# forkbomb19.net
KiCad netlist of a schematic drawn in EAGLE
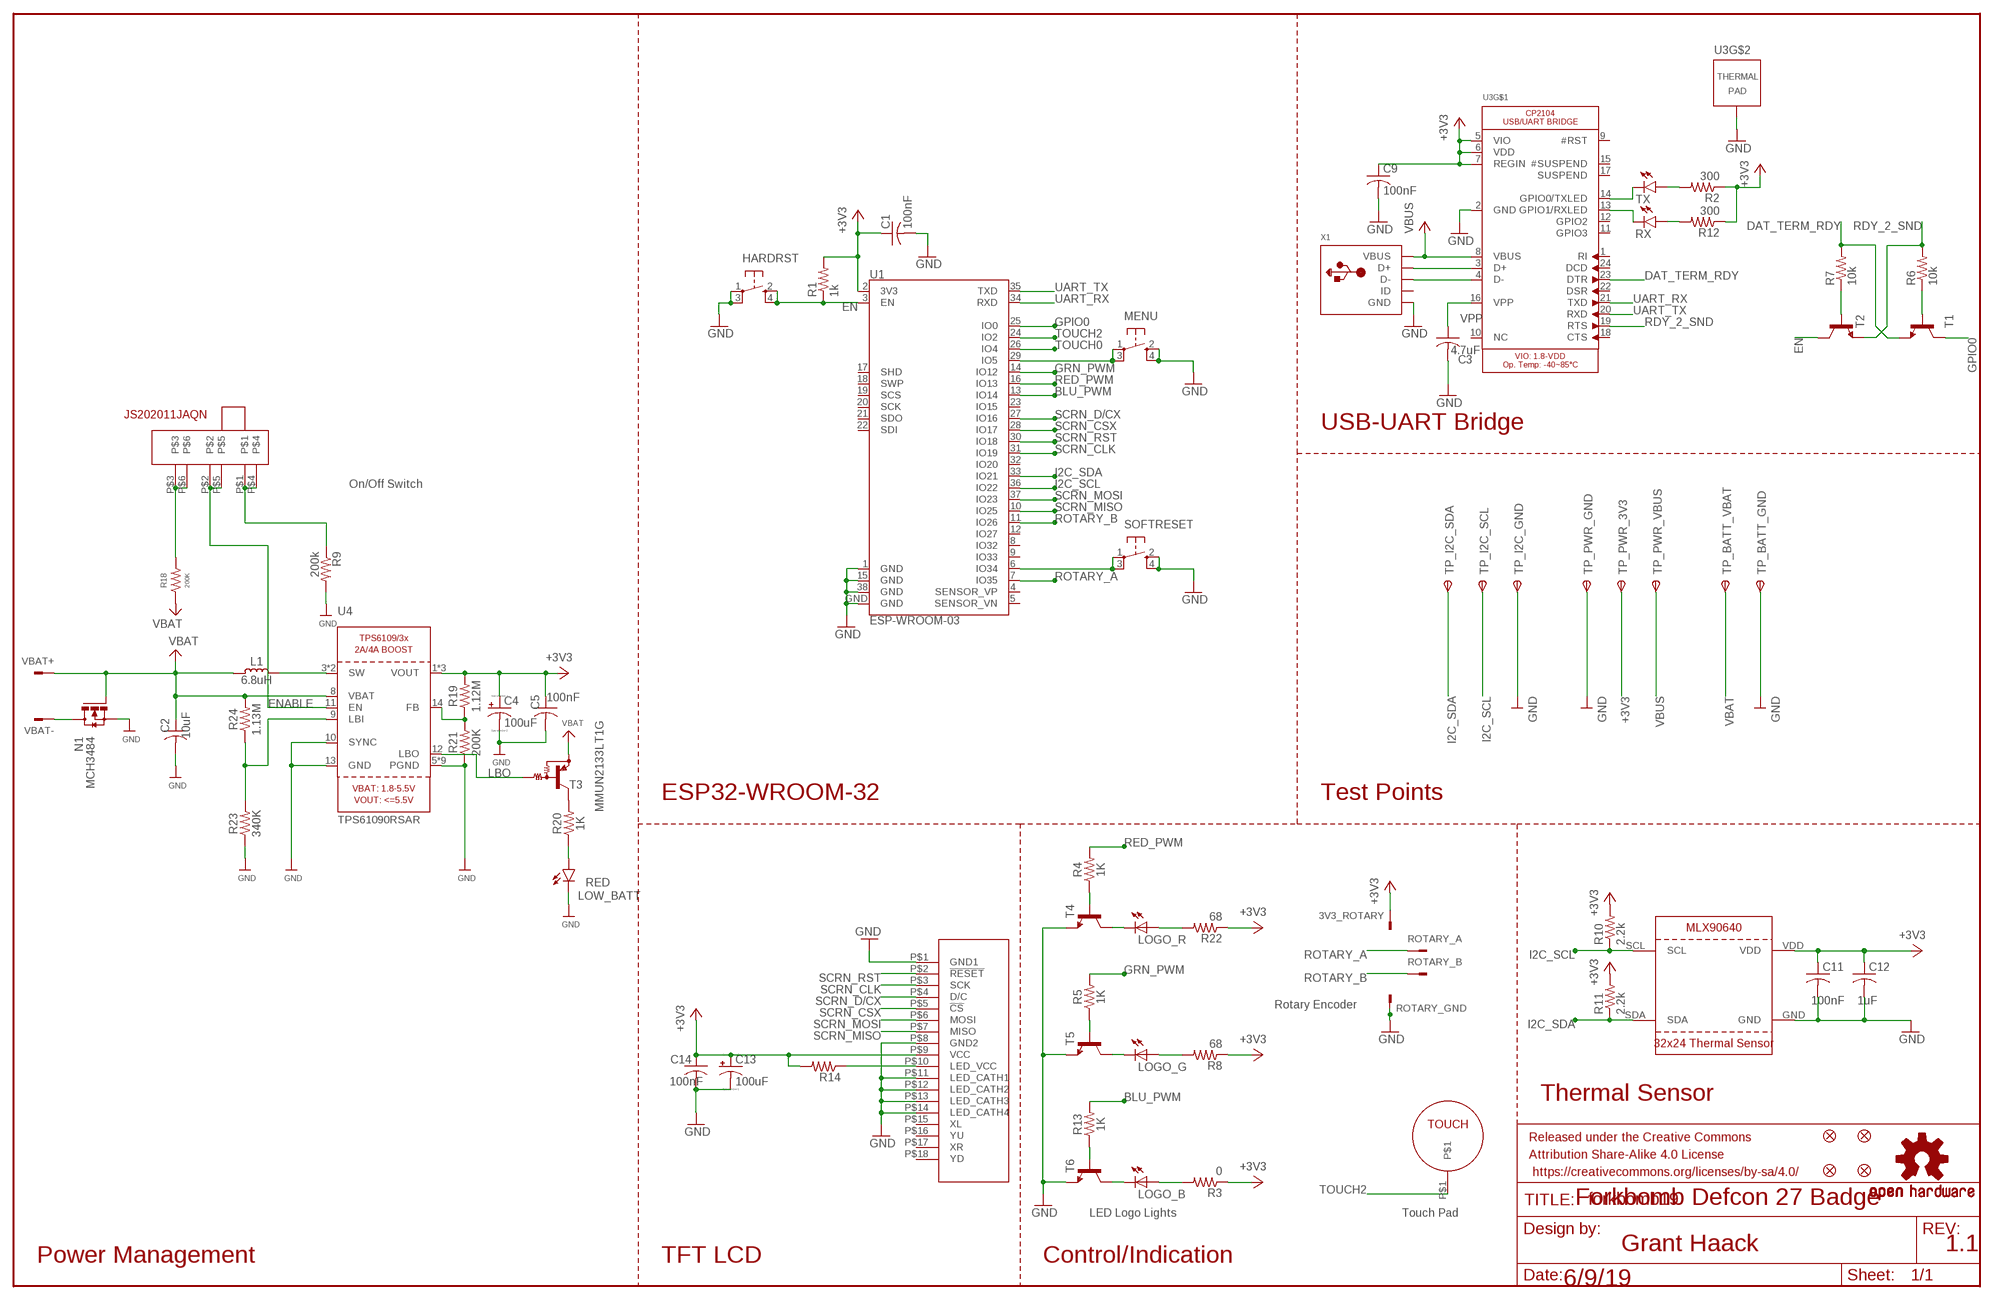
[diagram p0: schematic, sheet 1]

(export (version "E")
  (design (tool "Eeschema 10.0.6"))
  (components
    (comp (ref "3V3_ROTARY")
      (value "POT_GND")
      (footprint "eagle-import:TSW-101-XX-G-S")
      (fields (field (name "MF") "Samtec Inc.") (field (name "MPN") "TSW-101-07-G-S"))
      (libsource (lib "eagle-import") (part "TSW-101--G-S07"))
    )
    (comp (ref "C1")
      (value "100nF")
      (footprint "eagle-import:C0603")
      (libsource (lib "eagle-import") (part "resistor_348_C-USC0603"))
    )
    (comp (ref "C2")
      (value "10uF")
      (footprint "eagle-import:C1210")
      (libsource (lib "eagle-import") (part "C-USC1210"))
    )
    (comp (ref "C3")
      (value "4.7uF")
      (footprint "eagle-import:C0805")
      (libsource (lib "eagle-import") (part "C-USC0805"))
    )
    (comp (ref "C4")
      (value "100uF")
      (footprint "eagle-import:C_6032-28R")
      (libsource (lib "eagle-import") (part "CPOL-USC/6032-28R"))
    )
    (comp (ref "C5")
      (value "100nF")
      (footprint "eagle-import:C0603")
      (libsource (lib "eagle-import") (part "C-USC0603"))
    )
    (comp (ref "C9")
      (value "100nF")
      (footprint "eagle-import:C0603")
      (libsource (lib "eagle-import") (part "resistor_348_C-USC0603"))
    )
    (comp (ref "C11")
      (value "100nF")
      (footprint "eagle-import:C0603")
      (libsource (lib "eagle-import") (part "resistor_348_C-USC0603"))
    )
    (comp (ref "C12")
      (value "1uF")
      (footprint "eagle-import:C0805")
      (libsource (lib "eagle-import") (part "resistor_348_C-USC0805"))
    )
    (comp (ref "C13")
      (value "100uF")
      (footprint "eagle-import:C_6032-28R")
      (libsource (lib "eagle-import") (part "CPOL-USC/6032-28R"))
    )
    (comp (ref "C14")
      (value "100nF")
      (footprint "eagle-import:C0603")
      (libsource (lib "eagle-import") (part "resistor_348_C-USC0603"))
    )
    (comp (ref "FID1")
      (value "FIDUCIAL_1MM")
      (footprint "eagle-import:FIDUCIAL_1MM")
      (libsource (lib "eagle-import") (part "FIDUCIAL_1MM"))
    )
    (comp (ref "FID2")
      (value "FIDUCIAL_1MM")
      (footprint "eagle-import:FIDUCIAL_1MM")
      (libsource (lib "eagle-import") (part "FIDUCIAL_1MM"))
    )
    (comp (ref "FID3")
      (value "FIDUCIAL_1MM")
      (footprint "eagle-import:FIDUCIAL_1MM")
      (libsource (lib "eagle-import") (part "FIDUCIAL_1MM"))
    )
    (comp (ref "FID4")
      (value "FIDUCIAL_1MM")
      (footprint "eagle-import:FIDUCIAL_1MM")
      (libsource (lib "eagle-import") (part "FIDUCIAL_1MM"))
    )
    (comp (ref "FRAME1")
      (value "FRAME-LEDGER")
      (footprint "eagle-import:CREATIVE_COMMONS")
      (libsource (lib "eagle-import") (part "FRAME-LEDGER"))
    )
    (comp (ref "HARDRST")
      (value "SPST_TACT-KMR2")
      (footprint "eagle-import:KMR2")
      (libsource (lib "eagle-import") (part "SPST_TACT-KMR2"))
    )
    (comp (ref "L1")
      (value "6.8uH")
      (footprint "eagle-import:INDUCTOR_5X5MM_TDK_VLC5045")
      (libsource (lib "eagle-import") (part "INDUCTORTDK_VLC5045"))
    )
    (comp (ref "LOGO1")
      (value "OSHW-LOGOS-COPPER")
      (footprint "eagle-import:OSHW-LOGO-S_COPPER")
      (libsource (lib "eagle-import") (part "OSHW-LOGOS-COPPER"))
    )
    (comp (ref "LOGO_B")
      (value "REVERSE_PLCC_LED")
      (footprint "eagle-import:PLCC2_LED")
      (libsource (lib "eagle-import") (part "REVERSE_PLCC_LED"))
    )
    (comp (ref "LOGO_G")
      (value "REVERSE_PLCC_LED")
      (footprint "eagle-import:PLCC2_LED")
      (libsource (lib "eagle-import") (part "REVERSE_PLCC_LED"))
    )
    (comp (ref "LOGO_R")
      (value "REVERSE_PLCC_LED")
      (footprint "eagle-import:PLCC2_LED")
      (libsource (lib "eagle-import") (part "REVERSE_PLCC_LED"))
    )
    (comp (ref "LOW_BATT")
      (value "RED")
      (footprint "eagle-import:CHIP-LED0603")
      (libsource (lib "eagle-import") (part "LEDCHIP-LED0603"))
    )
    (comp (ref "MENU")
      (value "SPST_TACT-KMR2")
      (footprint "eagle-import:KMR2")
      (libsource (lib "eagle-import") (part "SPST_TACT-KMR2"))
    )
    (comp (ref "N1")
      (value "MCH3484")
      (footprint "eagle-import:MCH3484")
      (libsource (lib "eagle-import") (part "MCH3484"))
    )
    (comp (ref "R1")
      (value "1k")
      (footprint "eagle-import:R0603")
      (libsource (lib "eagle-import") (part "resistor_348_R-US_R0603"))
    )
    (comp (ref "R2")
      (value "300")
      (footprint "eagle-import:R0603")
      (libsource (lib "eagle-import") (part "resistor_348_R-US_R0603"))
    )
    (comp (ref "R3")
      (value "0")
      (footprint "eagle-import:R0805")
      (libsource (lib "eagle-import") (part "resistor_348_R-US_R0805"))
    )
    (comp (ref "R4")
      (value "1K")
      (footprint "eagle-import:R0603")
      (libsource (lib "eagle-import") (part "R-US_R0603"))
    )
    (comp (ref "R5")
      (value "1K")
      (footprint "eagle-import:R0603")
      (libsource (lib "eagle-import") (part "R-US_R0603"))
    )
    (comp (ref "R6")
      (value "10k")
      (footprint "eagle-import:R0603")
      (libsource (lib "eagle-import") (part "resistor_348_R-US_R0603"))
    )
    (comp (ref "R7")
      (value "10k")
      (footprint "eagle-import:R0603")
      (libsource (lib "eagle-import") (part "resistor_348_R-US_R0603"))
    )
    (comp (ref "R8")
      (value "68")
      (footprint "eagle-import:R0805")
      (libsource (lib "eagle-import") (part "resistor_348_R-US_R0805"))
    )
    (comp (ref "R9")
      (value "200k")
      (footprint "eagle-import:R0603")
      (libsource (lib "eagle-import") (part "R-US_R0603"))
    )
    (comp (ref "R10")
      (value "2.2k")
      (footprint "eagle-import:R0603")
      (libsource (lib "eagle-import") (part "resistor_348_R-US_R0603"))
    )
    (comp (ref "R11")
      (value "2.2k")
      (footprint "eagle-import:R0603")
      (libsource (lib "eagle-import") (part "resistor_348_R-US_R0603"))
    )
    (comp (ref "R12")
      (value "300")
      (footprint "eagle-import:R0603")
      (libsource (lib "eagle-import") (part "resistor_348_R-US_R0603"))
    )
    (comp (ref "R13")
      (value "1K")
      (footprint "eagle-import:R0603")
      (libsource (lib "eagle-import") (part "R-US_R0603"))
    )
    (comp (ref "R14")
      (value "R-US_R1210")
      (footprint "eagle-import:R1210")
      (libsource (lib "eagle-import") (part "R-US_R1210"))
    )
    (comp (ref "R18")
      (value "200K")
      (footprint "eagle-import:R0603")
      (libsource (lib "eagle-import") (part "R-US_R0603"))
    )
    (comp (ref "R19")
      (value "1.12M")
      (footprint "eagle-import:R0603")
      (libsource (lib "eagle-import") (part "R-US_R0603"))
    )
    (comp (ref "R20")
      (value "1K")
      (footprint "eagle-import:R0603")
      (libsource (lib "eagle-import") (part "R-US_R0603"))
    )
    (comp (ref "R21")
      (value "200K")
      (footprint "eagle-import:R0603")
      (libsource (lib "eagle-import") (part "R-US_R0603"))
    )
    (comp (ref "R22")
      (value "68")
      (footprint "eagle-import:R0805")
      (libsource (lib "eagle-import") (part "resistor_348_R-US_R0805"))
    )
    (comp (ref "R23")
      (value "340K")
      (footprint "eagle-import:R0603")
      (libsource (lib "eagle-import") (part "R-US_R0603"))
    )
    (comp (ref "R24")
      (value "1.13M")
      (footprint "eagle-import:R0603")
      (libsource (lib "eagle-import") (part "R-US_R0603"))
    )
    (comp (ref "ROTARY_A")
      (value "POT_SIG")
      (footprint "eagle-import:TSW-101-XX-G-S")
      (fields (field (name "MF") "Samtec Inc.") (field (name "MPN") "TSW-101-07-G-S"))
      (libsource (lib "eagle-import") (part "TSW-101--G-S07"))
    )
    (comp (ref "ROTARY_B")
      (value "POT_3V3")
      (footprint "eagle-import:TSW-101-XX-G-S")
      (fields (field (name "MF") "Samtec Inc.") (field (name "MPN") "TSW-101-07-G-S"))
      (libsource (lib "eagle-import") (part "TSW-101--G-S07"))
    )
    (comp (ref "ROTARY_GND")
      (value "POT_GND")
      (footprint "eagle-import:TSW-101-XX-G-S")
      (fields (field (name "MF") "Samtec Inc.") (field (name "MPN") "TSW-101-07-G-S"))
      (libsource (lib "eagle-import") (part "TSW-101--G-S07"))
    )
    (comp (ref "RX")
      (value "LEDCHIP-LED0603")
      (footprint "eagle-import:CHIP-LED0603")
      (libsource (lib "eagle-import") (part "LEDCHIP-LED0603"))
    )
    (comp (ref "SOFTRESET")
      (value "SPST_TACT-KMR2")
      (footprint "eagle-import:KMR2")
      (libsource (lib "eagle-import") (part "SPST_TACT-KMR2"))
    )
    (comp (ref "T1")
      (value "MMBT3904LT1-NPN-SOT23-BEC")
      (footprint "eagle-import:SOT23-BEC")
      (libsource (lib "eagle-import") (part "-NPN-SOT23-BECMMBT3904LT1"))
    )
    (comp (ref "T2")
      (value "MMBT3904LT1-NPN-SOT23-BEC")
      (footprint "eagle-import:SOT23-BEC")
      (libsource (lib "eagle-import") (part "-NPN-SOT23-BECMMBT3904LT1"))
    )
    (comp (ref "T3")
      (value "MMUN2133LT1G")
      (footprint "eagle-import:SC59-BEC")
      (libsource (lib "eagle-import") (part "-PNP_DRIVER-SC59-BECMUN2114T1"))
    )
    (comp (ref "T4")
      (value "MMBT3904LT1-NPN-SOT23-BEC")
      (footprint "eagle-import:SOT23-BEC")
      (libsource (lib "eagle-import") (part "-NPN-SOT23-BECMMBT3904LT1"))
    )
    (comp (ref "T5")
      (value "MMBT3904LT1-NPN-SOT23-BEC")
      (footprint "eagle-import:SOT23-BEC")
      (libsource (lib "eagle-import") (part "-NPN-SOT23-BECMMBT3904LT1"))
    )
    (comp (ref "T6")
      (value "MMBT3904LT1-NPN-SOT23-BEC")
      (footprint "eagle-import:SOT23-BEC")
      (libsource (lib "eagle-import") (part "-NPN-SOT23-BECMMBT3904LT1"))
    )
    (comp (ref "TOUCH")
      (value "TOUCHPADTOUCH_BLANK")
      (footprint "eagle-import:TOUCH_BLANK")
      (libsource (lib "eagle-import") (part "TOUCHPADTOUCH_BLANK"))
    )
    (comp (ref "TP_BATT_GND")
      (value "TPSTP20SQ")
      (footprint "eagle-import:TP20SQ")
      (libsource (lib "eagle-import") (part "TPSTP20SQ"))
    )
    (comp (ref "TP_BATT_VBAT")
      (value "TPSTP20SQ")
      (footprint "eagle-import:TP20SQ")
      (libsource (lib "eagle-import") (part "TPSTP20SQ"))
    )
    (comp (ref "TP_I2C_GND")
      (value "TPSTP20SQ")
      (footprint "eagle-import:TP20SQ")
      (libsource (lib "eagle-import") (part "TPSTP20SQ"))
    )
    (comp (ref "TP_I2C_SCL")
      (value "TPSTP20SQ")
      (footprint "eagle-import:TP20SQ")
      (libsource (lib "eagle-import") (part "TPSTP20SQ"))
    )
    (comp (ref "TP_I2C_SDA")
      (value "TPSTP20SQ")
      (footprint "eagle-import:TP20SQ")
      (libsource (lib "eagle-import") (part "TPSTP20SQ"))
    )
    (comp (ref "TP_PWR_3V3")
      (value "TPSTP20SQ")
      (footprint "eagle-import:TP20SQ")
      (libsource (lib "eagle-import") (part "TPSTP20SQ"))
    )
    (comp (ref "TP_PWR_GND")
      (value "TPSTP20SQ")
      (footprint "eagle-import:TP20SQ")
      (libsource (lib "eagle-import") (part "TPSTP20SQ"))
    )
    (comp (ref "TP_PWR_VBUS")
      (value "TPSTP20SQ")
      (footprint "eagle-import:TP20SQ")
      (libsource (lib "eagle-import") (part "TPSTP20SQ"))
    )
    (comp (ref "TX")
      (value "LEDCHIP-LED0603")
      (footprint "eagle-import:CHIP-LED0603")
      (libsource (lib "eagle-import") (part "LEDCHIP-LED0603"))
    )
    (comp (ref "U$2")
      (value "SPI_TFT")
      (footprint "eagle-import:SPI_TFT")
      (libsource (lib "eagle-import") (part "SPI_TFT"))
    )
    (comp (ref "U$7")
      (value "MLX90640")
      (footprint "eagle-import:MLX90640")
      (libsource (lib "eagle-import") (part "MLX90640"))
    )
    (comp (ref "U$8")
      (value "JS202011JAQN")
      (footprint "eagle-import:JS202011JAQN")
      (libsource (lib "eagle-import") (part "JS202011JAQN"))
    )
    (comp (ref "U1")
      (value "ESP-WROOM-03")
      (footprint "eagle-import:ESP-WROOM-03")
      (libsource (lib "eagle-import") (part "ESP-WROOM-03"))
    )
    (comp (ref "U3")
      (value "CP2104")
      (footprint "eagle-import:QFN24_4MM_SMSC")
      (libsource (lib "eagle-import") (part "CP2104"))
    )
    (comp (ref "U4")
      (value "TPS61090RSAR")
      (footprint "eagle-import:PVQFN-16")
      (libsource (lib "eagle-import") (part "VREG_TPS6103X"))
    )
    (comp (ref "VBAT+")
      (value "POT_GND")
      (footprint "eagle-import:TSW-101-XX-G-S")
      (fields (field (name "MF") "Samtec Inc.") (field (name "MPN") "TSW-101-07-G-S"))
      (libsource (lib "eagle-import") (part "TSW-101--G-S07"))
    )
    (comp (ref "VBAT-")
      (value "POT_GND")
      (footprint "eagle-import:TSW-101-XX-G-S")
      (fields (field (name "MF") "Samtec Inc.") (field (name "MPN") "TSW-101-07-G-S"))
      (libsource (lib "eagle-import") (part "TSW-101--G-S07"))
    )
    (comp (ref "X1")
      (value "USB_MICRO_20329_V2")
      (footprint "eagle-import:4UCONN_20329_V2")
      (libsource (lib "eagle-import") (part "USB_MICRO_20329_V2"))
    )
  )
  (nets
    (net (code "1") (name "+3V3") (class "Default")
      (node (ref "3V3_ROTARY") (pin "1") (pinfunction "1_1") (pintype "passive"))
      (node (ref "C1") (pin "1") (pinfunction "1_1") (pintype "passive"))
      (node (ref "C11") (pin "1") (pinfunction "1_1") (pintype "passive"))
      (node (ref "C12") (pin "1") (pinfunction "1_1") (pintype "passive"))
      (node (ref "C13") (pin "+") (pinfunction "+_+") (pintype "passive"))
      (node (ref "C14") (pin "1") (pinfunction "1_1") (pintype "passive"))
      (node (ref "C4") (pin "+") (pinfunction "+_+") (pintype "passive"))
      (node (ref "C5") (pin "1") (pinfunction "1_1") (pintype "passive"))
      (node (ref "C9") (pin "1") (pinfunction "1_1") (pintype "passive"))
      (node (ref "R1") (pin "2") (pinfunction "2_2") (pintype "passive"))
      (node (ref "R10") (pin "2") (pinfunction "2_2") (pintype "passive"))
      (node (ref "R11") (pin "2") (pinfunction "2_2") (pintype "passive"))
      (node (ref "R12") (pin "1") (pinfunction "1_1") (pintype "passive"))
      (node (ref "R14") (pin "2") (pinfunction "2_2") (pintype "passive"))
      (node (ref "R19") (pin "2") (pinfunction "2_2") (pintype "passive"))
      (node (ref "R2") (pin "1") (pinfunction "1_1") (pintype "passive"))
      (node (ref "R22") (pin "1") (pinfunction "1_1") (pintype "passive"))
      (node (ref "R3") (pin "1") (pinfunction "1_1") (pintype "passive"))
      (node (ref "R8") (pin "1") (pinfunction "1_1") (pintype "passive"))
      (node (ref "TP_PWR_3V3") (pin "TP") (pinfunction "PP_TP") (pintype "input"))
      (node (ref "U$2") (pin "P$9") (pinfunction "VCC_P$9") (pintype "bidirectional"))
      (node (ref "U$7") (pin "VDD") (pinfunction "VDD_VDD") (pintype "bidirectional"))
      (node (ref "U1") (pin "2") (pinfunction "3V3_2") (pintype "bidirectional"))
      (node (ref "U3") (pin "5") (pinfunction "VIO_5") (pintype "power_in"))
      (node (ref "U3") (pin "6") (pinfunction "VDD_6") (pintype "power_in"))
      (node (ref "U3") (pin "7") (pinfunction "REGIN_7") (pintype "power_in"))
      (node (ref "U4") (pin "1") (pinfunction "VOUT_1") (pintype "power_in"))
      (node (ref "U4") (pin "15") (pinfunction "VOUT_15") (pintype "power_in"))
      (node (ref "U4") (pin "16") (pinfunction "VOUT_16") (pintype "power_in"))
    )
    (net (code "2") (name "/BLU_PWM") (class "Default")
      (node (ref "R13") (pin "2") (pinfunction "2_2") (pintype "passive"))
      (node (ref "U1") (pin "13") (pinfunction "IO14_13") (pintype "bidirectional"))
    )
    (net (code "3") (name "/DAT_TERM_RDY") (class "Default")
      (node (ref "R7") (pin "2") (pinfunction "2_2") (pintype "passive"))
      (node (ref "T1") (pin "E") (pinfunction "E_E") (pintype "passive"))
      (node (ref "U3") (pin "23") (pinfunction "DTR_23") (pintype "output"))
    )
    (net (code "4") (name "/EN") (class "Default")
      (node (ref "HARDRST") (pin "2") (pinfunction "S_2") (pintype "passive"))
      (node (ref "HARDRST") (pin "4") (pinfunction "S1_4") (pintype "passive"))
      (node (ref "R1") (pin "1") (pinfunction "1_1") (pintype "passive"))
      (node (ref "T2") (pin "C") (pinfunction "C_C") (pintype "passive"))
      (node (ref "U1") (pin "3") (pinfunction "EN_3") (pintype "bidirectional"))
    )
    (net (code "5") (name "/ENABLE") (class "Default")
      (node (ref "U$8") (pin "P$2") (pinfunction "P$2_P$2") (pintype "bidirectional"))
      (node (ref "U$8") (pin "P$5") (pinfunction "P$5_P$5") (pintype "bidirectional"))
      (node (ref "U4") (pin "11") (pinfunction "EN_11") (pintype "input"))
    )
    (net (code "6") (name "/GPIO0") (class "Default")
      (node (ref "T1") (pin "C") (pinfunction "C_C") (pintype "passive"))
      (node (ref "U1") (pin "25") (pinfunction "IO0_25") (pintype "bidirectional"))
    )
    (net (code "7") (name "/GRN_PWM") (class "Default")
      (node (ref "R5") (pin "2") (pinfunction "2_2") (pintype "passive"))
      (node (ref "U1") (pin "14") (pinfunction "IO12_14") (pintype "bidirectional"))
    )
    (net (code "8") (name "/I2C_SCL") (class "Default")
      (node (ref "R10") (pin "1") (pinfunction "1_1") (pintype "passive"))
      (node (ref "TP_I2C_SCL") (pin "TP") (pinfunction "PP_TP") (pintype "input"))
      (node (ref "U$7") (pin "SCL") (pinfunction "SCL_SCL") (pintype "bidirectional"))
      (node (ref "U1") (pin "36") (pinfunction "IO22_36") (pintype "bidirectional"))
    )
    (net (code "9") (name "/I2C_SDA") (class "Default")
      (node (ref "R11") (pin "1") (pinfunction "1_1") (pintype "passive"))
      (node (ref "TP_I2C_SDA") (pin "TP") (pinfunction "PP_TP") (pintype "input"))
      (node (ref "U$7") (pin "SDA") (pinfunction "SDA_SDA") (pintype "bidirectional"))
      (node (ref "U1") (pin "33") (pinfunction "IO21_33") (pintype "bidirectional"))
    )
    (net (code "10") (name "/LBO") (class "Default")
      (node (ref "T3") (pin "B") (pinfunction "B_B") (pintype "passive"))
      (node (ref "U4") (pin "12") (pinfunction "LBO_12") (pintype "output"))
    )
    (net (code "11") (name "/RDY_2_SND") (class "Default")
      (node (ref "R6") (pin "2") (pinfunction "2_2") (pintype "passive"))
      (node (ref "T2") (pin "E") (pinfunction "E_E") (pintype "passive"))
      (node (ref "U3") (pin "19") (pinfunction "RTS_19") (pintype "output"))
    )
    (net (code "12") (name "/RED_PWM") (class "Default")
      (node (ref "R4") (pin "2") (pinfunction "2_2") (pintype "passive"))
      (node (ref "U1") (pin "16") (pinfunction "IO13_16") (pintype "bidirectional"))
    )
    (net (code "13") (name "/ROTARY_A") (class "Default")
      (node (ref "ROTARY_A") (pin "1") (pinfunction "1_1") (pintype "passive"))
      (node (ref "U1") (pin "7") (pinfunction "IO35_7") (pintype "bidirectional"))
    )
    (net (code "14") (name "/ROTARY_B") (class "Default")
      (node (ref "ROTARY_B") (pin "1") (pinfunction "1_1") (pintype "passive"))
      (node (ref "U1") (pin "11") (pinfunction "IO26_11") (pintype "bidirectional"))
    )
    (net (code "15") (name "/SCRN_CLK") (class "Default")
      (node (ref "U$2") (pin "P$3") (pinfunction "SCK_P$3") (pintype "bidirectional"))
      (node (ref "U1") (pin "31") (pinfunction "IO19_31") (pintype "bidirectional"))
    )
    (net (code "16") (name "/SCRN_CSX") (class "Default")
      (node (ref "U$2") (pin "P$5") (pinfunction "~{CS}_P$5") (pintype "bidirectional"))
      (node (ref "U1") (pin "28") (pinfunction "IO17_28") (pintype "bidirectional"))
    )
    (net (code "17") (name "/SCRN_D{slash}CX") (class "Default")
      (node (ref "U$2") (pin "P$4") (pinfunction "D/C_P$4") (pintype "bidirectional"))
      (node (ref "U1") (pin "27") (pinfunction "IO16_27") (pintype "bidirectional"))
    )
    (net (code "18") (name "/SCRN_MISO") (class "Default")
      (node (ref "U$2") (pin "P$7") (pinfunction "MISO_P$7") (pintype "bidirectional"))
      (node (ref "U1") (pin "10") (pinfunction "IO25_10") (pintype "bidirectional"))
    )
    (net (code "19") (name "/SCRN_MOSI") (class "Default")
      (node (ref "U$2") (pin "P$6") (pinfunction "MOSI_P$6") (pintype "bidirectional"))
      (node (ref "U1") (pin "37") (pinfunction "IO23_37") (pintype "bidirectional"))
    )
    (net (code "20") (name "/SCRN_RST") (class "Default")
      (node (ref "U$2") (pin "P$2") (pinfunction "~{RESET}_P$2") (pintype "bidirectional"))
      (node (ref "U1") (pin "30") (pinfunction "IO18_30") (pintype "bidirectional"))
    )
    (net (code "21") (name "/TOUCH0") (class "Default")
      (node (ref "U1") (pin "26") (pinfunction "IO4_26") (pintype "bidirectional"))
    )
    (net (code "22") (name "/TOUCH2") (class "Default")
      (node (ref "TOUCH") (pin "P$1") (pinfunction "P$1_P$1") (pintype "bidirectional"))
      (node (ref "U1") (pin "24") (pinfunction "IO2_24") (pintype "bidirectional"))
    )
    (net (code "23") (name "/UART_RX") (class "Default")
      (node (ref "U1") (pin "34") (pinfunction "RXD_34") (pintype "bidirectional"))
      (node (ref "U3") (pin "21") (pinfunction "TXD_21") (pintype "output"))
    )
    (net (code "24") (name "/UART_TX") (class "Default")
      (node (ref "U1") (pin "35") (pinfunction "TXD_35") (pintype "bidirectional"))
      (node (ref "U3") (pin "20") (pinfunction "RXD_20") (pintype "input"))
    )
    (net (code "25") (name "/VPP") (class "Default")
      (node (ref "C3") (pin "1") (pinfunction "1_1") (pintype "passive"))
      (node (ref "U3") (pin "16") (pinfunction "VPP_16") (pintype "bidirectional"))
    )
    (net (code "26") (name "GND") (class "Default")
      (node (ref "C1") (pin "2") (pinfunction "2_2") (pintype "passive"))
      (node (ref "C11") (pin "2") (pinfunction "2_2") (pintype "passive"))
      (node (ref "C12") (pin "2") (pinfunction "2_2") (pintype "passive"))
      (node (ref "C13") (pin "-") (pinfunction "-_-") (pintype "passive"))
      (node (ref "C14") (pin "2") (pinfunction "2_2") (pintype "passive"))
      (node (ref "C2") (pin "2") (pinfunction "2_2") (pintype "passive"))
      (node (ref "C3") (pin "2") (pinfunction "2_2") (pintype "passive"))
      (node (ref "C4") (pin "-") (pinfunction "-_-") (pintype "passive"))
      (node (ref "C5") (pin "2") (pinfunction "2_2") (pintype "passive"))
      (node (ref "C9") (pin "2") (pinfunction "2_2") (pintype "passive"))
      (node (ref "HARDRST") (pin "1") (pinfunction "P_1") (pintype "passive"))
      (node (ref "HARDRST") (pin "3") (pinfunction "P1_3") (pintype "passive"))
      (node (ref "LOW_BATT") (pin "C") (pinfunction "C_C") (pintype "passive"))
      (node (ref "MENU") (pin "2") (pinfunction "S_2") (pintype "passive"))
      (node (ref "MENU") (pin "4") (pinfunction "S1_4") (pintype "passive"))
      (node (ref "N1") (pin "S") (pinfunction "S_S") (pintype "passive"))
      (node (ref "R21") (pin "1") (pinfunction "1_1") (pintype "passive"))
      (node (ref "R23") (pin "1") (pinfunction "1_1") (pintype "passive"))
      (node (ref "R9") (pin "2") (pinfunction "2_2") (pintype "passive"))
      (node (ref "ROTARY_GND") (pin "1") (pinfunction "1_1") (pintype "passive"))
      (node (ref "SOFTRESET") (pin "2") (pinfunction "S_2") (pintype "passive"))
      (node (ref "SOFTRESET") (pin "4") (pinfunction "S1_4") (pintype "passive"))
      (node (ref "T4") (pin "E") (pinfunction "E_E") (pintype "passive"))
      (node (ref "T5") (pin "E") (pinfunction "E_E") (pintype "passive"))
      (node (ref "T6") (pin "E") (pinfunction "E_E") (pintype "passive"))
      (node (ref "TP_BATT_GND") (pin "TP") (pinfunction "PP_TP") (pintype "input"))
      (node (ref "TP_I2C_GND") (pin "TP") (pinfunction "PP_TP") (pintype "input"))
      (node (ref "TP_PWR_GND") (pin "TP") (pinfunction "PP_TP") (pintype "input"))
      (node (ref "U$2") (pin "P$1") (pinfunction "GND1_P$1") (pintype "bidirectional"))
      (node (ref "U$2") (pin "P$11") (pinfunction "LED_CATH1_P$11") (pintype "bidirectional"))
      (node (ref "U$2") (pin "P$12") (pinfunction "LED_CATH2_P$12") (pintype "bidirectional"))
      (node (ref "U$2") (pin "P$13") (pinfunction "LED_CATH3_P$13") (pintype "bidirectional"))
      (node (ref "U$2") (pin "P$14") (pinfunction "LED_CATH4_P$14") (pintype "bidirectional"))
      (node (ref "U$2") (pin "P$8") (pinfunction "GND2_P$8") (pintype "bidirectional"))
      (node (ref "U$7") (pin "GND") (pinfunction "GND_GND") (pintype "bidirectional"))
      (node (ref "U1") (pin "1") (pinfunction "GND_1") (pintype "bidirectional"))
      (node (ref "U1") (pin "15") (pinfunction "GND_15") (pintype "bidirectional"))
      (node (ref "U1") (pin "38") (pinfunction "GND_38") (pintype "bidirectional"))
      (node (ref "U1") (pin "GND") (pinfunction "GND_GND") (pintype "bidirectional"))
      (node (ref "U3") (pin "2") (pinfunction "GND_2") (pintype "power_in"))
      (node (ref "U3") (pin "THERM") (pinfunction "TP_THERM") (pintype "power_in"))
      (node (ref "U4") (pin "10") (pinfunction "SYNC_10") (pintype "input"))
      (node (ref "U4") (pin "13") (pinfunction "GND_13") (pintype "power_in"))
      (node (ref "U4") (pin "5") (pinfunction "PGND_5") (pintype "power_in"))
      (node (ref "U4") (pin "6") (pinfunction "PGND_6") (pintype "power_in"))
      (node (ref "U4") (pin "7") (pinfunction "PGND_7") (pintype "power_in"))
      (node (ref "U4") (pin "P$18") (pinfunction "PGND_P$18") (pintype "power_in"))
      (node (ref "U4") (pin "P$19") (pinfunction "PGND_P$19") (pintype "power_in"))
      (node (ref "U4") (pin "P$20") (pinfunction "PGND_P$20") (pintype "power_in"))
      (node (ref "U4") (pin "P$21") (pinfunction "PGND_P$21") (pintype "power_in"))
      (node (ref "U4") (pin "P$22") (pinfunction "PGND_P$22") (pintype "power_in"))
      (node (ref "U4") (pin "THERMAL") (pinfunction "PGND_THERMAL") (pintype "power_in"))
      (node (ref "X1") (pin "BASE@1") (pinfunction "GND_BASE@1") (pintype "power_in"))
      (node (ref "X1") (pin "BASE@2") (pinfunction "GND_BASE@2") (pintype "power_in"))
      (node (ref "X1") (pin "GND") (pinfunction "GND_GND") (pintype "power_in"))
      (node (ref "X1") (pin "SPRT@1") (pinfunction "GND_SPRT@1") (pintype "power_in"))
      (node (ref "X1") (pin "SPRT@2") (pinfunction "GND_SPRT@2") (pintype "power_in"))
      (node (ref "X1") (pin "SPRT@3") (pinfunction "GND_SPRT@3") (pintype "power_in"))
      (node (ref "X1") (pin "SPRT@4") (pinfunction "GND_SPRT@4") (pintype "power_in"))
    )
    (net (code "27") (name "Net-(L1-2)") (class "Default")
      (node (ref "L1") (pin "P$2") (pinfunction "2_P$2") (pintype "passive"))
      (node (ref "U4") (pin "3") (pinfunction "SW_3") (pintype "input"))
      (node (ref "U4") (pin "4") (pinfunction "SW_4") (pintype "input"))
    )
    (net (code "28") (name "Net-(LOGO_B-A)") (class "Default")
      (node (ref "LOGO_B") (pin "1") (pinfunction "A_1") (pintype "passive"))
      (node (ref "R3") (pin "2") (pinfunction "2_2") (pintype "passive"))
    )
    (net (code "29") (name "Net-(LOGO_B-C)") (class "Default")
      (node (ref "LOGO_B") (pin "2") (pinfunction "C_2") (pintype "passive"))
      (node (ref "T6") (pin "C") (pinfunction "C_C") (pintype "passive"))
    )
    (net (code "30") (name "Net-(LOGO_G-A)") (class "Default")
      (node (ref "LOGO_G") (pin "1") (pinfunction "A_1") (pintype "passive"))
      (node (ref "R8") (pin "2") (pinfunction "2_2") (pintype "passive"))
    )
    (net (code "31") (name "Net-(LOGO_G-C)") (class "Default")
      (node (ref "LOGO_G") (pin "2") (pinfunction "C_2") (pintype "passive"))
      (node (ref "T5") (pin "C") (pinfunction "C_C") (pintype "passive"))
    )
    (net (code "32") (name "Net-(LOGO_R-A)") (class "Default")
      (node (ref "LOGO_R") (pin "1") (pinfunction "A_1") (pintype "passive"))
      (node (ref "R22") (pin "2") (pinfunction "2_2") (pintype "passive"))
    )
    (net (code "33") (name "Net-(LOGO_R-C)") (class "Default")
      (node (ref "LOGO_R") (pin "2") (pinfunction "C_2") (pintype "passive"))
      (node (ref "T4") (pin "C") (pinfunction "C_C") (pintype "passive"))
    )
    (net (code "34") (name "Net-(LOW_BATT-PadA)") (class "Default")
      (node (ref "LOW_BATT") (pin "A") (pinfunction "A_A") (pintype "passive"))
      (node (ref "R20") (pin "1") (pinfunction "1_1") (pintype "passive"))
    )
    (net (code "35") (name "Net-(MENU-P)") (class "Default")
      (node (ref "MENU") (pin "1") (pinfunction "P_1") (pintype "passive"))
      (node (ref "MENU") (pin "3") (pinfunction "P1_3") (pintype "passive"))
      (node (ref "U1") (pin "29") (pinfunction "IO5_29") (pintype "bidirectional"))
    )
    (net (code "36") (name "Net-(N1-PadD)") (class "Default")
      (node (ref "N1") (pin "D") (pinfunction "D_D") (pintype "passive"))
      (node (ref "VBAT-") (pin "1") (pinfunction "1_1") (pintype "passive"))
    )
    (net (code "37") (name "Net-(R2-Pad2)") (class "Default")
      (node (ref "R2") (pin "2") (pinfunction "2_2") (pintype "passive"))
      (node (ref "TX") (pin "A") (pinfunction "A_A") (pintype "passive"))
    )
    (net (code "38") (name "Net-(R4-Pad1)") (class "Default")
      (node (ref "R4") (pin "1") (pinfunction "1_1") (pintype "passive"))
      (node (ref "T4") (pin "B") (pinfunction "B_B") (pintype "passive"))
    )
    (net (code "39") (name "Net-(R5-Pad1)") (class "Default")
      (node (ref "R5") (pin "1") (pinfunction "1_1") (pintype "passive"))
      (node (ref "T5") (pin "B") (pinfunction "B_B") (pintype "passive"))
    )
    (net (code "40") (name "Net-(R6-Pad1)") (class "Default")
      (node (ref "R6") (pin "1") (pinfunction "1_1") (pintype "passive"))
      (node (ref "T1") (pin "B") (pinfunction "B_B") (pintype "passive"))
    )
    (net (code "41") (name "Net-(R7-Pad1)") (class "Default")
      (node (ref "R7") (pin "1") (pinfunction "1_1") (pintype "passive"))
      (node (ref "T2") (pin "B") (pinfunction "B_B") (pintype "passive"))
    )
    (net (code "42") (name "Net-(R9-Pad1)") (class "Default")
      (node (ref "R9") (pin "1") (pinfunction "1_1") (pintype "passive"))
      (node (ref "U$8") (pin "P$1") (pinfunction "P$1_P$1") (pintype "bidirectional"))
      (node (ref "U$8") (pin "P$4") (pinfunction "P$4_P$4") (pintype "bidirectional"))
    )
    (net (code "43") (name "Net-(R12-Pad2)") (class "Default")
      (node (ref "R12") (pin "2") (pinfunction "2_2") (pintype "passive"))
      (node (ref "RX") (pin "A") (pinfunction "A_A") (pintype "passive"))
    )
    (net (code "44") (name "Net-(R13-Pad1)") (class "Default")
      (node (ref "R13") (pin "1") (pinfunction "1_1") (pintype "passive"))
      (node (ref "T6") (pin "B") (pinfunction "B_B") (pintype "passive"))
    )
    (net (code "45") (name "Net-(R18-Pad2)") (class "Default")
      (node (ref "R18") (pin "2") (pinfunction "2_2") (pintype "passive"))
      (node (ref "U$8") (pin "P$3") (pinfunction "P$3_P$3") (pintype "bidirectional"))
      (node (ref "U$8") (pin "P$6") (pinfunction "P$6_P$6") (pintype "bidirectional"))
    )
    (net (code "46") (name "Net-(R20-Pad2)") (class "Default")
      (node (ref "R20") (pin "2") (pinfunction "2_2") (pintype "passive"))
      (node (ref "T3") (pin "C") (pinfunction "C_C") (pintype "passive"))
    )
    (net (code "47") (name "Net-(SOFTRESET-P)") (class "Default")
      (node (ref "SOFTRESET") (pin "1") (pinfunction "P_1") (pintype "passive"))
      (node (ref "SOFTRESET") (pin "3") (pinfunction "P1_3") (pintype "passive"))
      (node (ref "U1") (pin "6") (pinfunction "IO34_6") (pintype "bidirectional"))
    )
    (net (code "48") (name "Net-(U$2-LED_VCC)") (class "Default")
      (node (ref "R14") (pin "1") (pinfunction "1_1") (pintype "passive"))
      (node (ref "U$2") (pin "P$10") (pinfunction "LED_VCC_P$10") (pintype "bidirectional"))
    )
    (net (code "49") (name "Net-(U3A-D+)") (class "Default")
      (node (ref "U3") (pin "3") (pinfunction "D+_3") (pintype "bidirectional"))
      (node (ref "X1") (pin "D+") (pinfunction "D+_D+") (pintype "bidirectional"))
    )
    (net (code "50") (name "Net-(U3A-D-)") (class "Default")
      (node (ref "U3") (pin "4") (pinfunction "D-_4") (pintype "bidirectional"))
      (node (ref "X1") (pin "D-") (pinfunction "D-_D-") (pintype "bidirectional"))
    )
    (net (code "51") (name "Net-(U3A-GPIO0{slash}TXLED)") (class "Default")
      (node (ref "TX") (pin "C") (pinfunction "C_C") (pintype "passive"))
      (node (ref "U3") (pin "14") (pinfunction "GPIO0/TXLED_14") (pintype "bidirectional"))
    )
    (net (code "52") (name "Net-(U3A-GPIO1{slash}RXLED)") (class "Default")
      (node (ref "RX") (pin "C") (pinfunction "C_C") (pintype "passive"))
      (node (ref "U3") (pin "13") (pinfunction "GPIO1/RXLED_13") (pintype "bidirectional"))
    )
    (net (code "53") (name "Net-(U4-FB)") (class "Default")
      (node (ref "R19") (pin "1") (pinfunction "1_1") (pintype "passive"))
      (node (ref "R21") (pin "2") (pinfunction "2_2") (pintype "passive"))
      (node (ref "U4") (pin "14") (pinfunction "FB_14") (pintype "input"))
    )
    (net (code "54") (name "Net-(U4-LBI)") (class "Default")
      (node (ref "R23") (pin "2") (pinfunction "2_2") (pintype "passive"))
      (node (ref "R24") (pin "1") (pinfunction "1_1") (pintype "passive"))
      (node (ref "U4") (pin "9") (pinfunction "LBI_9") (pintype "input"))
    )
    (net (code "55") (name "VBAT") (class "Default")
      (node (ref "C2") (pin "1") (pinfunction "1_1") (pintype "passive"))
      (node (ref "L1") (pin "P$1") (pinfunction "1_P$1") (pintype "passive"))
      (node (ref "N1") (pin "G") (pinfunction "G_G") (pintype "passive"))
      (node (ref "R18") (pin "1") (pinfunction "1_1") (pintype "passive"))
      (node (ref "R24") (pin "2") (pinfunction "2_2") (pintype "passive"))
      (node (ref "T3") (pin "E") (pinfunction "E_E") (pintype "passive"))
      (node (ref "TP_BATT_VBAT") (pin "TP") (pinfunction "PP_TP") (pintype "input"))
      (node (ref "U4") (pin "8") (pinfunction "VBAT_8") (pintype "input"))
      (node (ref "VBAT+") (pin "1") (pinfunction "1_1") (pintype "passive"))
    )
    (net (code "56") (name "VBUS") (class "Default")
      (node (ref "TP_PWR_VBUS") (pin "TP") (pinfunction "PP_TP") (pintype "input"))
      (node (ref "U3") (pin "8") (pinfunction "VBUS_8") (pintype "power_in"))
      (node (ref "X1") (pin "VBUS") (pinfunction "VBUS_VBUS") (pintype "power_in"))
    )
    (net (code "57") (name "unconnected-(U$2-XL-PadP$15)") (class "Default")
      (node (ref "U$2") (pin "P$15") (pinfunction "XL_P$15") (pintype "bidirectional"))
    )
    (net (code "58") (name "unconnected-(U$2-XR-PadP$17)") (class "Default")
      (node (ref "U$2") (pin "P$17") (pinfunction "XR_P$17") (pintype "bidirectional"))
    )
    (net (code "59") (name "unconnected-(U$2-YD-PadP$18)") (class "Default")
      (node (ref "U$2") (pin "P$18") (pinfunction "YD_P$18") (pintype "bidirectional"))
    )
    (net (code "60") (name "unconnected-(U$2-YU-PadP$16)") (class "Default")
      (node (ref "U$2") (pin "P$16") (pinfunction "YU_P$16") (pintype "bidirectional"))
    )
    (net (code "61") (name "unconnected-(U1-IO15-Pad23)") (class "Default")
      (node (ref "U1") (pin "23") (pinfunction "IO15_23") (pintype "bidirectional"))
    )
    (net (code "62") (name "unconnected-(U1-IO20-Pad32)") (class "Default")
      (node (ref "U1") (pin "32") (pinfunction "IO20_32") (pintype "bidirectional"))
    )
    (net (code "63") (name "unconnected-(U1-IO27-Pad12)") (class "Default")
      (node (ref "U1") (pin "12") (pinfunction "IO27_12") (pintype "bidirectional"))
    )
    (net (code "64") (name "unconnected-(U1-IO32-Pad8)") (class "Default")
      (node (ref "U1") (pin "8") (pinfunction "IO32_8") (pintype "bidirectional"))
    )
    (net (code "65") (name "unconnected-(U1-IO33-Pad9)") (class "Default")
      (node (ref "U1") (pin "9") (pinfunction "IO33_9") (pintype "bidirectional"))
    )
    (net (code "66") (name "unconnected-(U1-SCK-Pad20)") (class "Default")
      (node (ref "U1") (pin "20") (pinfunction "SCK_20") (pintype "bidirectional"))
    )
    (net (code "67") (name "unconnected-(U1-SCS-Pad19)") (class "Default")
      (node (ref "U1") (pin "19") (pinfunction "SCS_19") (pintype "bidirectional"))
    )
    (net (code "68") (name "unconnected-(U1-SDI-Pad22)") (class "Default")
      (node (ref "U1") (pin "22") (pinfunction "SDI_22") (pintype "bidirectional"))
    )
    (net (code "69") (name "unconnected-(U1-SDO-Pad21)") (class "Default")
      (node (ref "U1") (pin "21") (pinfunction "SDO_21") (pintype "bidirectional"))
    )
    (net (code "70") (name "unconnected-(U1-SENSOR_VN-Pad5)") (class "Default")
      (node (ref "U1") (pin "5") (pinfunction "SENSOR_VN_5") (pintype "bidirectional"))
    )
    (net (code "71") (name "unconnected-(U1-SENSOR_VP-Pad4)") (class "Default")
      (node (ref "U1") (pin "4") (pinfunction "SENSOR_VP_4") (pintype "bidirectional"))
    )
    (net (code "72") (name "unconnected-(U1-SHD-Pad17)") (class "Default")
      (node (ref "U1") (pin "17") (pinfunction "SHD_17") (pintype "bidirectional"))
    )
    (net (code "73") (name "unconnected-(U1-SWP-Pad18)") (class "Default")
      (node (ref "U1") (pin "18") (pinfunction "SWP_18") (pintype "bidirectional"))
    )
    (net (code "74") (name "unconnected-(U3A-#RST-Pad9)") (class "Default")
      (node (ref "U3") (pin "9") (pinfunction "#RST_9") (pintype "bidirectional"))
    )
    (net (code "75") (name "unconnected-(U3A-#SUSPEND-Pad15)") (class "Default")
      (node (ref "U3") (pin "15") (pinfunction "#SUSPEND_15") (pintype "output"))
    )
    (net (code "76") (name "unconnected-(U3A-CTS-Pad18)") (class "Default")
      (node (ref "U3") (pin "18") (pinfunction "CTS_18") (pintype "input"))
    )
    (net (code "77") (name "unconnected-(U3A-DCD-Pad24)") (class "Default")
      (node (ref "U3") (pin "24") (pinfunction "DCD_24") (pintype "input"))
    )
    (net (code "78") (name "unconnected-(U3A-DSR-Pad22)") (class "Default")
      (node (ref "U3") (pin "22") (pinfunction "DSR_22") (pintype "input"))
    )
    (net (code "79") (name "unconnected-(U3A-GPIO2-Pad12)") (class "Default")
      (node (ref "U3") (pin "12") (pinfunction "GPIO2_12") (pintype "bidirectional"))
    )
    (net (code "80") (name "unconnected-(U3A-GPIO3-Pad11)") (class "Default")
      (node (ref "U3") (pin "11") (pinfunction "GPIO3_11") (pintype "bidirectional"))
    )
    (net (code "81") (name "unconnected-(U3A-NC-Pad10)") (class "Default")
      (node (ref "U3") (pin "10") (pinfunction "NC_10") (pintype "no_connect"))
    )
    (net (code "82") (name "unconnected-(U3A-RI-Pad1)") (class "Default")
      (node (ref "U3") (pin "1") (pinfunction "RI_1") (pintype "input"))
    )
    (net (code "83") (name "unconnected-(U3A-SUSPEND-Pad17)") (class "Default")
      (node (ref "U3") (pin "17") (pinfunction "SUSPEND_17") (pintype "output"))
    )
    (net (code "84") (name "unconnected-(X1-PadID)") (class "Default")
      (node (ref "X1") (pin "ID") (pinfunction "ID_ID") (pintype "bidirectional"))
    )
  )
)
